# TPT02.net
KiCad netlist of a schematic drawn in EAGLE
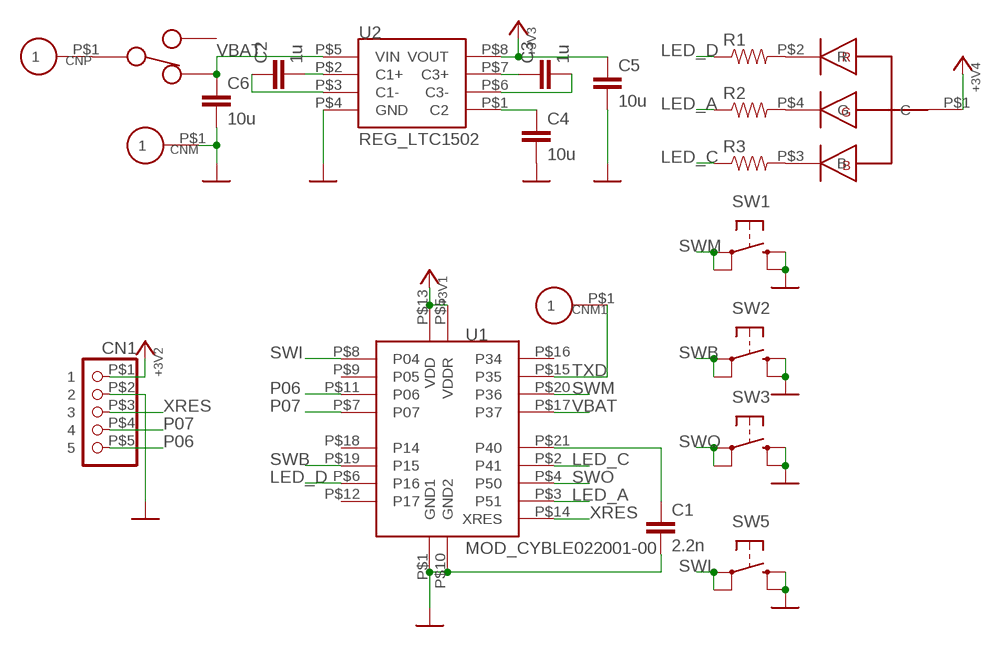
[diagram p0: schematic, sheet 1]

(export (version "E")
  (design (tool "Eeschema 10.0.6"))
  (components
    (comp (ref "C1")
      (value "2.2n")
      (footprint "eagle-import:0603")
      (libsource (lib "eagle-import") (part "CAP0603"))
    )
    (comp (ref "C2")
      (value "1u")
      (footprint "eagle-import:0603")
      (libsource (lib "eagle-import") (part "CAP0603"))
    )
    (comp (ref "C3")
      (value "1u")
      (footprint "eagle-import:0603")
      (libsource (lib "eagle-import") (part "CAP0603"))
    )
    (comp (ref "C4")
      (value "10u")
      (footprint "eagle-import:0603")
      (libsource (lib "eagle-import") (part "CAP0603"))
    )
    (comp (ref "C5")
      (value "10u")
      (footprint "eagle-import:0603")
      (libsource (lib "eagle-import") (part "CAP0603"))
    )
    (comp (ref "C6")
      (value "10u")
      (footprint "eagle-import:0603")
      (libsource (lib "eagle-import") (part "CAP0603"))
    )
    (comp (ref "CN1")
      (value "CON_PINHD-1X550MIL")
      (footprint "eagle-import:1X5_50MIL")
      (libsource (lib "eagle-import") (part "CON_PINHD-1X550MIL"))
    )
    (comp (ref "CNM")
      (value "CON_P01SMD1MM")
      (footprint "eagle-import:PAD_SMD1MM")
      (libsource (lib "eagle-import") (part "CON_P01SMD1MM"))
    )
    (comp (ref "CNM1")
      (value "CON_P01SMD1MM")
      (footprint "eagle-import:PAD_SMD1MM")
      (libsource (lib "eagle-import") (part "CON_P01SMD1MM"))
    )
    (comp (ref "CNP")
      (value "CON_P01SMD1MM")
      (footprint "eagle-import:PAD_SMD1MM")
      (libsource (lib "eagle-import") (part "CON_P01SMD1MM"))
    )
    (comp (ref "D1")
      (value "LED_RGB_OSTB0603C1C")
      (footprint "eagle-import:LED_0606_4P")
      (libsource (lib "eagle-import") (part "LED_RGB_OSTB0603C1C"))
    )
    (comp (ref "R1")
      (value "RES0603")
      (footprint "eagle-import:0603")
      (libsource (lib "eagle-import") (part "RES0603"))
    )
    (comp (ref "R2")
      (value "RES0603")
      (footprint "eagle-import:0603")
      (libsource (lib "eagle-import") (part "RES0603"))
    )
    (comp (ref "R3")
      (value "RES0603")
      (footprint "eagle-import:0603")
      (libsource (lib "eagle-import") (part "RES0603"))
    )
    (comp (ref "SW1")
      (value "SW_TACTEVQP2")
      (footprint "eagle-import:SW_EVQP2")
      (libsource (lib "eagle-import") (part "SW_TACTEVQP2"))
    )
    (comp (ref "SW2")
      (value "SW_TACTTSKA2J")
      (footprint "eagle-import:SW_TSKA-2JL")
      (libsource (lib "eagle-import") (part "SW_TACTTSKA2J"))
    )
    (comp (ref "SW3")
      (value "SW_TACTTSKA2J")
      (footprint "eagle-import:SW_TSKA-2JL")
      (libsource (lib "eagle-import") (part "SW_TACTTSKA2J"))
    )
    (comp (ref "SW4")
      (value "SW_SLIDECUS12")
      (footprint "eagle-import:SW_CUS-12B")
      (libsource (lib "eagle-import") (part "SW_SLIDECUS12"))
    )
    (comp (ref "SW5")
      (value "SW_TACTEVQPU02")
      (footprint "eagle-import:SW_EVQPUA02")
      (libsource (lib "eagle-import") (part "SW_TACTEVQPU02"))
    )
    (comp (ref "U1")
      (value "MOD_CYBLE022001-00")
      (footprint "eagle-import:MOD_CYBLE022001-00")
      (libsource (lib "eagle-import") (part "MOD_CYBLE022001-00"))
    )
    (comp (ref "U2")
      (value "REG_LTC1502")
      (footprint "eagle-import:MSOP8")
      (libsource (lib "eagle-import") (part "REG_LTC1502"))
    )
  )
  (nets
    (net (code "1") (name "/LED_A") (class "Default")
      (node (ref "R2") (pin "1") (pinfunction "1_1") (pintype "passive"))
      (node (ref "U1") (pin "P$3") (pinfunction "P51_P$3") (pintype "bidirectional"))
    )
    (net (code "2") (name "/LED_C") (class "Default")
      (node (ref "R3") (pin "1") (pinfunction "1_1") (pintype "passive"))
      (node (ref "U1") (pin "P$2") (pinfunction "P41_P$2") (pintype "bidirectional"))
    )
    (net (code "3") (name "/LED_D") (class "Default")
      (node (ref "R1") (pin "1") (pinfunction "1_1") (pintype "passive"))
      (node (ref "U1") (pin "P$6") (pinfunction "P16_P$6") (pintype "bidirectional"))
    )
    (net (code "4") (name "/P$3") (class "Default")
      (node (ref "SW4") (pin "P$3") (pinfunction "P$3_P$3") (pintype "power_in"))
    )
    (net (code "5") (name "/P06") (class "Default")
      (node (ref "CN1") (pin "P$5") (pinfunction "5_P$5") (pintype "passive"))
      (node (ref "U1") (pin "P$11") (pinfunction "P06_P$11") (pintype "bidirectional"))
    )
    (net (code "6") (name "/P07") (class "Default")
      (node (ref "CN1") (pin "P$4") (pinfunction "4_P$4") (pintype "passive"))
      (node (ref "U1") (pin "P$7") (pinfunction "P07_P$7") (pintype "bidirectional"))
    )
    (net (code "7") (name "/SWB") (class "Default")
      (node (ref "SW2") (pin "PA1") (pinfunction "P_PA1") (pintype "passive"))
      (node (ref "SW2") (pin "PA2") (pinfunction "P1_PA2") (pintype "passive"))
      (node (ref "U1") (pin "P$19") (pinfunction "P15_P$19") (pintype "bidirectional"))
    )
    (net (code "8") (name "/SWI") (class "Default")
      (node (ref "SW5") (pin "PA1") (pinfunction "P_PA1") (pintype "passive"))
      (node (ref "SW5") (pin "PA2") (pinfunction "P1_PA2") (pintype "passive"))
      (node (ref "U1") (pin "P$8") (pinfunction "P04_P$8") (pintype "bidirectional"))
    )
    (net (code "9") (name "/SWM") (class "Default")
      (node (ref "SW1") (pin "PA1") (pinfunction "P_PA1") (pintype "passive"))
      (node (ref "SW1") (pin "PA2") (pinfunction "P1_PA2") (pintype "passive"))
      (node (ref "U1") (pin "P$20") (pinfunction "P36_P$20") (pintype "bidirectional"))
    )
    (net (code "10") (name "/SWO") (class "Default")
      (node (ref "SW3") (pin "PA1") (pinfunction "P_PA1") (pintype "passive"))
      (node (ref "SW3") (pin "PA2") (pinfunction "P1_PA2") (pintype "passive"))
      (node (ref "U1") (pin "P$4") (pinfunction "P50_P$4") (pintype "bidirectional"))
    )
    (net (code "11") (name "/TXD") (class "Default")
      (node (ref "CNM1") (pin "P$1") (pinfunction "1_P$1") (pintype "bidirectional"))
      (node (ref "U1") (pin "P$15") (pinfunction "P35_P$15") (pintype "bidirectional"))
    )
    (net (code "12") (name "/VBAT") (class "Default")
      (node (ref "C6") (pin "1") (pinfunction "1_1") (pintype "passive"))
      (node (ref "SW4") (pin "P$1") (pinfunction "P$1_P$1") (pintype "power_in"))
      (node (ref "U1") (pin "P$17") (pinfunction "P37_P$17") (pintype "bidirectional"))
      (node (ref "U2") (pin "P$5") (pinfunction "VIN_P$5") (pintype "bidirectional"))
    )
    (net (code "13") (name "/XRES") (class "Default")
      (node (ref "CN1") (pin "P$3") (pinfunction "3_P$3") (pintype "passive"))
      (node (ref "U1") (pin "P$14") (pinfunction "XRES_P$14") (pintype "bidirectional"))
    )
    (net (code "14") (name "Net-(CNP-1)") (class "Default")
      (node (ref "CNP") (pin "P$1") (pinfunction "1_P$1") (pintype "bidirectional"))
      (node (ref "SW4") (pin "P$2") (pinfunction "P$2_P$2") (pintype "power_in"))
    )
    (net (code "15") (name "Net-(D1-B)") (class "Default")
      (node (ref "D1") (pin "P$3") (pinfunction "B_P$3") (pintype "bidirectional"))
      (node (ref "R3") (pin "2") (pinfunction "2_2") (pintype "passive"))
    )
    (net (code "16") (name "Net-(D1-G)") (class "Default")
      (node (ref "D1") (pin "P$4") (pinfunction "G_P$4") (pintype "bidirectional"))
      (node (ref "R2") (pin "2") (pinfunction "2_2") (pintype "passive"))
    )
    (net (code "17") (name "Net-(D1-R)") (class "Default")
      (node (ref "D1") (pin "P$2") (pinfunction "R_P$2") (pintype "bidirectional"))
      (node (ref "R1") (pin "2") (pinfunction "2_2") (pintype "passive"))
    )
    (net (code "18") (name "Net-(U1-P40)") (class "Default")
      (node (ref "C1") (pin "1") (pinfunction "1_1") (pintype "passive"))
      (node (ref "U1") (pin "P$21") (pinfunction "P40_P$21") (pintype "bidirectional"))
    )
    (net (code "19") (name "Net-(U2-C1+)") (class "Default")
      (node (ref "C2") (pin "2") (pinfunction "2_2") (pintype "passive"))
      (node (ref "U2") (pin "P$2") (pinfunction "C1+_P$2") (pintype "bidirectional"))
    )
    (net (code "20") (name "Net-(U2-C1-)") (class "Default")
      (node (ref "C2") (pin "1") (pinfunction "1_1") (pintype "passive"))
      (node (ref "U2") (pin "P$3") (pinfunction "C1-_P$3") (pintype "bidirectional"))
    )
    (net (code "21") (name "Net-(U2-C2)") (class "Default")
      (node (ref "C4") (pin "1") (pinfunction "1_1") (pintype "passive"))
      (node (ref "U2") (pin "P$1") (pinfunction "C2_P$1") (pintype "bidirectional"))
    )
    (net (code "22") (name "Net-(U2-C3+)") (class "Default")
      (node (ref "C3") (pin "1") (pinfunction "1_1") (pintype "passive"))
      (node (ref "U2") (pin "P$7") (pinfunction "C3+_P$7") (pintype "bidirectional"))
    )
    (net (code "23") (name "Net-(U2-C3-)") (class "Default")
      (node (ref "C3") (pin "2") (pinfunction "2_2") (pintype "passive"))
      (node (ref "U2") (pin "P$6") (pinfunction "C3-_P$6") (pintype "bidirectional"))
    )
    (net (code "24") (name "POW_+3V3") (class "Default")
      (node (ref "C5") (pin "1") (pinfunction "1_1") (pintype "passive"))
      (node (ref "CN1") (pin "P$1") (pinfunction "1_P$1") (pintype "passive"))
      (node (ref "D1") (pin "P$1") (pinfunction "C_P$1") (pintype "bidirectional"))
      (node (ref "U1") (pin "P$13") (pinfunction "VDD_P$13") (pintype "bidirectional"))
      (node (ref "U1") (pin "P$5") (pinfunction "VDDR_P$5") (pintype "bidirectional"))
      (node (ref "U2") (pin "P$8") (pinfunction "VOUT_P$8") (pintype "bidirectional"))
    )
    (net (code "25") (name "POW_GND") (class "Default")
      (node (ref "C1") (pin "2") (pinfunction "2_2") (pintype "passive"))
      (node (ref "C4") (pin "2") (pinfunction "2_2") (pintype "passive"))
      (node (ref "C5") (pin "2") (pinfunction "2_2") (pintype "passive"))
      (node (ref "C6") (pin "2") (pinfunction "2_2") (pintype "passive"))
      (node (ref "CN1") (pin "P$2") (pinfunction "2_P$2") (pintype "passive"))
      (node (ref "CNM") (pin "P$1") (pinfunction "1_P$1") (pintype "bidirectional"))
      (node (ref "SW1") (pin "PB1") (pinfunction "S_PB1") (pintype "passive"))
      (node (ref "SW1") (pin "PB2") (pinfunction "S1_PB2") (pintype "passive"))
      (node (ref "SW2") (pin "PB1") (pinfunction "S_PB1") (pintype "passive"))
      (node (ref "SW2") (pin "PB2") (pinfunction "S1_PB2") (pintype "passive"))
      (node (ref "SW3") (pin "PB1") (pinfunction "S_PB1") (pintype "passive"))
      (node (ref "SW3") (pin "PB2") (pinfunction "S1_PB2") (pintype "passive"))
      (node (ref "SW5") (pin "PB1") (pinfunction "S_PB1") (pintype "passive"))
      (node (ref "SW5") (pin "PB2") (pinfunction "S1_PB2") (pintype "passive"))
      (node (ref "U1") (pin "P$1") (pinfunction "GND1_P$1") (pintype "bidirectional"))
      (node (ref "U1") (pin "P$10") (pinfunction "GND2_P$10") (pintype "bidirectional"))
      (node (ref "U2") (pin "P$4") (pinfunction "GND_P$4") (pintype "bidirectional"))
    )
    (net (code "26") (name "unconnected-(U1-P05-PadP$9)") (class "Default")
      (node (ref "U1") (pin "P$9") (pinfunction "P05_P$9") (pintype "bidirectional"))
    )
    (net (code "27") (name "unconnected-(U1-P14-PadP$18)") (class "Default")
      (node (ref "U1") (pin "P$18") (pinfunction "P14_P$18") (pintype "bidirectional"))
    )
    (net (code "28") (name "unconnected-(U1-P17-PadP$12)") (class "Default")
      (node (ref "U1") (pin "P$12") (pinfunction "P17_P$12") (pintype "bidirectional"))
    )
    (net (code "29") (name "unconnected-(U1-P34-PadP$16)") (class "Default")
      (node (ref "U1") (pin "P$16") (pinfunction "P34_P$16") (pintype "bidirectional"))
    )
  )
)
